# Sheet1.net
KiCad netlist of a schematic drawn in Altium Designer
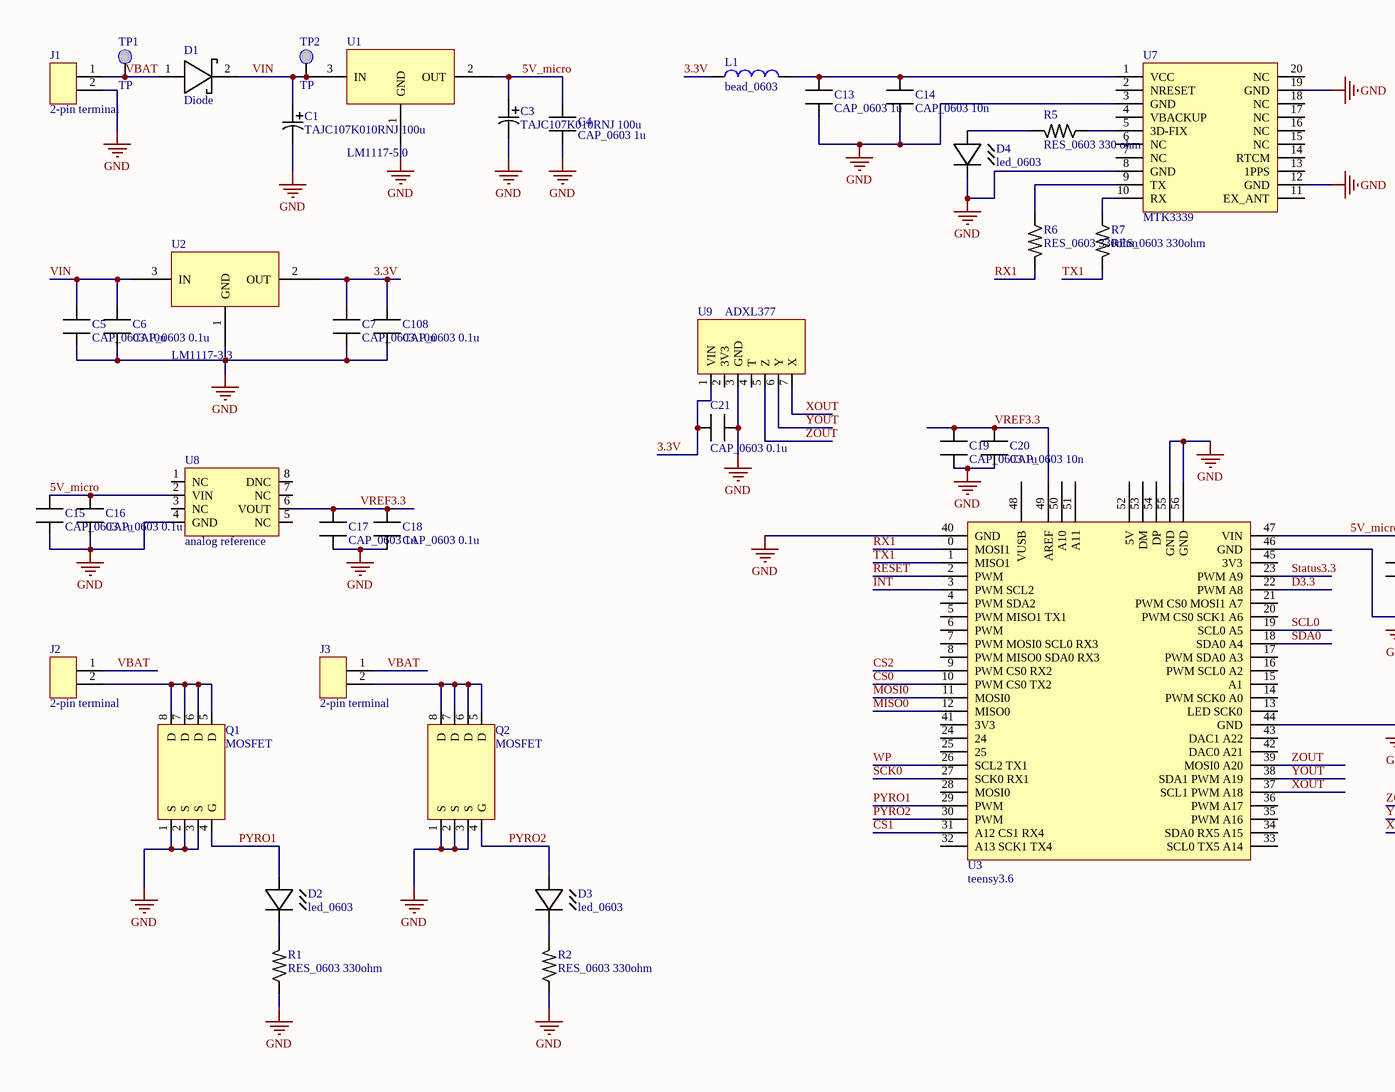
[diagram p0: Sheet1.SchDoc, left]
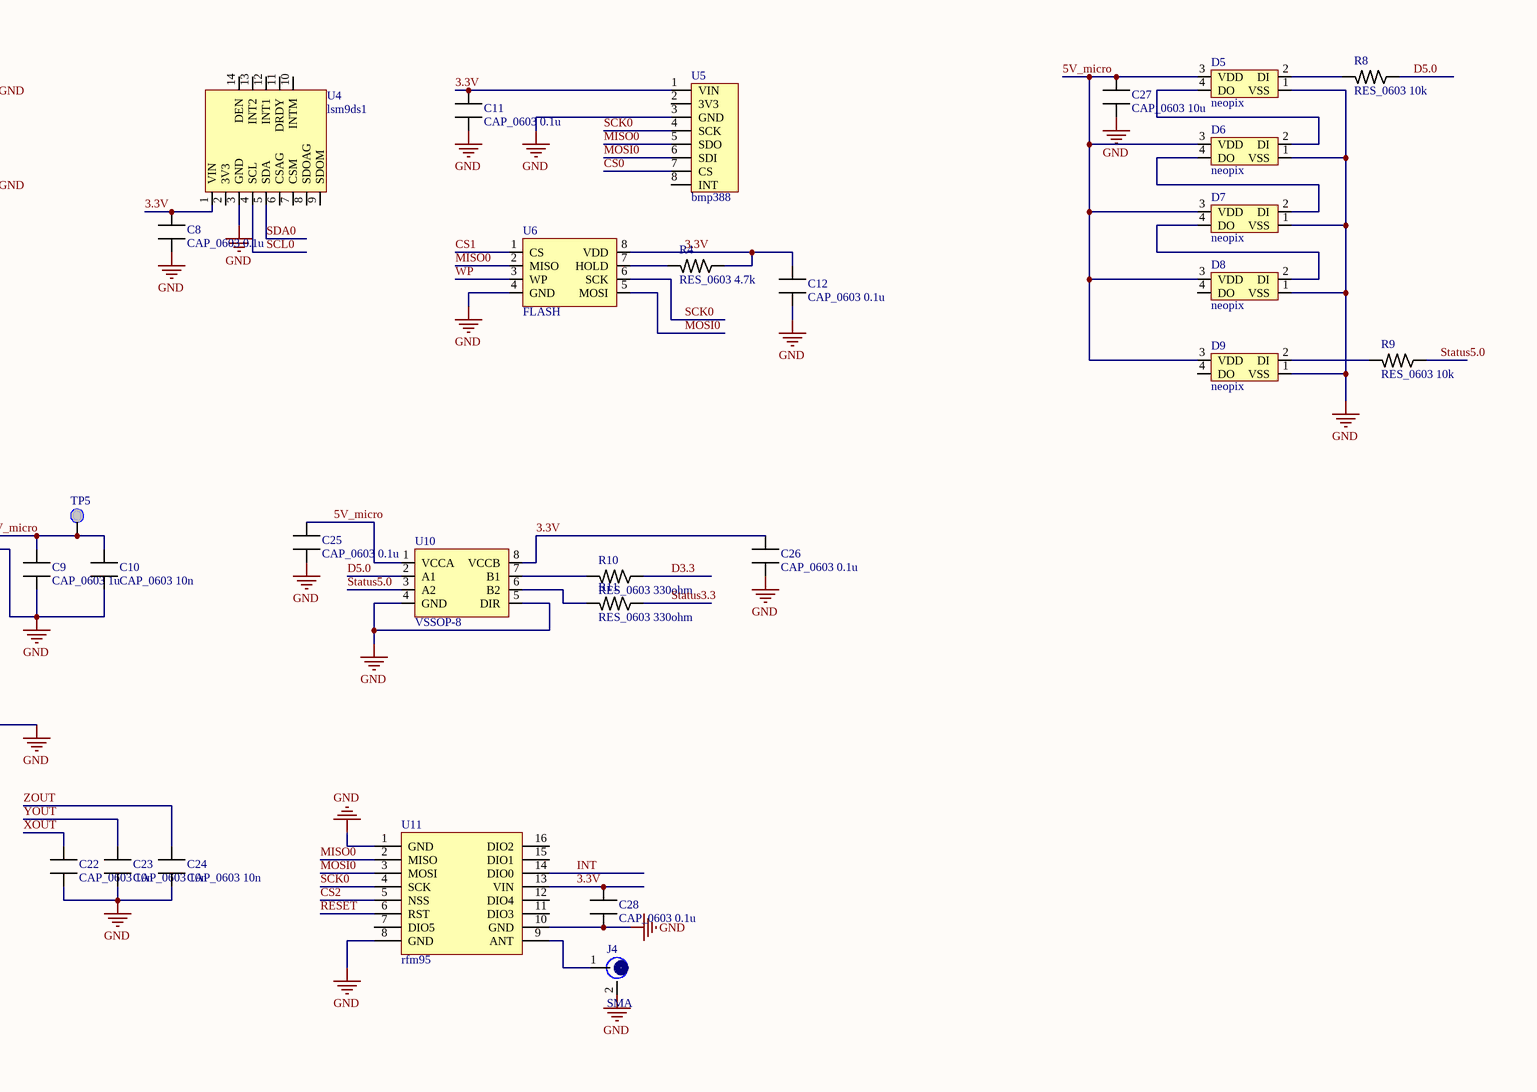
[diagram p1: Sheet1.SchDoc, right]

(export (version "E")
  (design (tool "Eeschema 10.0.6"))
  (components
    (comp (ref "C1")
      (value "TAJC107K010RNJ 100u")
      (footprint "TAJC")
      (description "100u")
      (fields
        (field (name "MANUFACTURER_PART_NUMBER") "TAJC107K010RNJ")
        (field (name "COPYRIGHT") "Copyright (C) 2018 Accelerated Designs. All rights reserved")
      )
      (libsource (lib "teensy_Integrated_Library1") (part "TAJC107K010RNJ"))
    )
    (comp (ref "C3")
      (value "TAJC107K010RNJ 100u")
      (footprint "TAJC")
      (description "No Description Available")
      (fields
        (field (name "MANUFACTURER_PART_NUMBER") "TAJC107K010RNJ")
        (field (name "COPYRIGHT") "Copyright (C) 2018 Accelerated Designs. All rights reserved")
      )
      (libsource (lib "teensy_Integrated_Library1") (part "TAJC107K010RNJ"))
    )
    (comp (ref "C4")
      (value "CAP_0603 1u")
      (footprint "CAP_0603")
      (description "CAP_0603")
      (libsource (lib "teensy_Integrated_Library1") (part "CAP_0603"))
    )
    (comp (ref "C5")
      (value "CAP_0603 10u")
      (footprint "CAP_0603")
      (description "CAP_0603")
      (libsource (lib "teensy_Integrated_Library1") (part "CAP_0603"))
    )
    (comp (ref "C6")
      (value "CAP_0603 0.1u")
      (footprint "CAP_0603")
      (description "CAP_0603")
      (libsource (lib "teensy_Integrated_Library1") (part "CAP_0603"))
    )
    (comp (ref "C7")
      (value "CAP_0603 10u")
      (footprint "CAP_0603")
      (description "CAP_0603")
      (libsource (lib "teensy_Integrated_Library1") (part "CAP_0603"))
    )
    (comp (ref "C8")
      (value "CAP_0603 0.1u")
      (footprint "CAP_0603")
      (description "CAP_0603")
      (libsource (lib "teensy_Integrated_Library1") (part "CAP_0603"))
    )
    (comp (ref "C9")
      (value "CAP_0603 1u")
      (footprint "CAP_0603")
      (description "CAP_0603")
      (libsource (lib "teensy_Integrated_Library1") (part "CAP_0603"))
    )
    (comp (ref "C10")
      (value "CAP_0603 10n")
      (footprint "CAP_0603")
      (description "CAP_0603")
      (libsource (lib "teensy_Integrated_Library1") (part "CAP_0603"))
    )
    (comp (ref "C11")
      (value "CAP_0603 0.1u")
      (footprint "CAP_0603")
      (description "CAP_0603")
      (libsource (lib "teensy_Integrated_Library1") (part "CAP_0603"))
    )
    (comp (ref "C12")
      (value "CAP_0603 0.1u")
      (footprint "CAP_0603")
      (description "CAP_0603")
      (libsource (lib "teensy_Integrated_Library1") (part "CAP_0603"))
    )
    (comp (ref "C13")
      (value "CAP_0603 1u")
      (footprint "CAP_0603")
      (description "CAP_0603")
      (libsource (lib "teensy_Integrated_Library1") (part "CAP_0603"))
    )
    (comp (ref "C14")
      (value "CAP_0603 10n")
      (footprint "CAP_0603")
      (description "CAP_0603")
      (libsource (lib "teensy_Integrated_Library1") (part "CAP_0603"))
    )
    (comp (ref "C15")
      (value "CAP_0603 1u")
      (footprint "CAP_0603")
      (description "CAP_0603")
      (libsource (lib "teensy_Integrated_Library1") (part "CAP_0603"))
    )
    (comp (ref "C16")
      (value "CAP_0603 0.1u")
      (footprint "CAP_0603")
      (description "CAP_0603")
      (libsource (lib "teensy_Integrated_Library1") (part "CAP_0603"))
    )
    (comp (ref "C17")
      (value "CAP_0603 1u")
      (footprint "CAP_0603")
      (description "CAP_0603")
      (libsource (lib "teensy_Integrated_Library1") (part "CAP_0603"))
    )
    (comp (ref "C18")
      (value "CAP_0603 0.1u")
      (footprint "CAP_0603")
      (description "CAP_0603")
      (libsource (lib "teensy_Integrated_Library1") (part "CAP_0603"))
    )
    (comp (ref "C19")
      (value "CAP_0603 1u")
      (footprint "CAP_0603")
      (description "CAP_0603")
      (libsource (lib "teensy_Integrated_Library1") (part "CAP_0603"))
    )
    (comp (ref "C20")
      (value "CAP_0603 10n")
      (footprint "CAP_0603")
      (description "CAP_0603")
      (libsource (lib "teensy_Integrated_Library1") (part "CAP_0603"))
    )
    (comp (ref "C21")
      (value "CAP_0603 0.1u")
      (footprint "CAP_0603")
      (description "CAP_0603")
      (libsource (lib "teensy_Integrated_Library1") (part "CAP_0603"))
    )
    (comp (ref "C22")
      (value "CAP_0603 10n")
      (footprint "CAP_0603")
      (description "CAP_0603")
      (libsource (lib "teensy_Integrated_Library1") (part "CAP_0603"))
    )
    (comp (ref "C23")
      (value "CAP_0603 10n")
      (footprint "CAP_0603")
      (description "CAP_0603")
      (libsource (lib "teensy_Integrated_Library1") (part "CAP_0603"))
    )
    (comp (ref "C24")
      (value "CAP_0603 10n")
      (footprint "CAP_0603")
      (description "CAP_0603")
      (libsource (lib "teensy_Integrated_Library1") (part "CAP_0603"))
    )
    (comp (ref "C25")
      (value "CAP_0603 0.1u")
      (footprint "CAP_0603")
      (description "CAP_0603")
      (libsource (lib "teensy_Integrated_Library1") (part "CAP_0603"))
    )
    (comp (ref "C26")
      (value "CAP_0603 0.1u")
      (footprint "CAP_0603")
      (description "CAP_0603")
      (libsource (lib "teensy_Integrated_Library1") (part "CAP_0603"))
    )
    (comp (ref "C27")
      (value "CAP_0603 10u")
      (footprint "CAP_0603")
      (description "CAP_0603")
      (libsource (lib "teensy_Integrated_Library1") (part "CAP_0603"))
    )
    (comp (ref "C28")
      (value "CAP_0603 0.1u")
      (footprint "CAP_0603")
      (description "CAP_0603")
      (libsource (lib "teensy_Integrated_Library1") (part "CAP_0603"))
    )
    (comp (ref "C108")
      (value "CAP_0603 0.1u")
      (footprint "CAP_0603")
      (description "CAP_0603")
      (libsource (lib "teensy_Integrated_Library1") (part "CAP_0603"))
    )
    (comp (ref "D1")
      (value "Diode")
      (footprint "RBR3LAM60BTF_diode")
      (libsource (lib "teensy_Integrated_Library1") (part "Diode"))
    )
    (comp (ref "D2")
      (value "led_0603")
      (footprint "LED_0603")
      (libsource (lib "teensy_Integrated_Library1") (part "led_0603"))
    )
    (comp (ref "D3")
      (value "led_0603")
      (footprint "LED_0603")
      (libsource (lib "teensy_Integrated_Library1") (part "led_0603"))
    )
    (comp (ref "D4")
      (value "led_0603")
      (footprint "LED_0603")
      (libsource (lib "teensy_Integrated_Library1") (part "led_0603"))
    )
    (comp (ref "D5")
      (value "neopix")
      (footprint "neopix")
      (libsource (lib "teensy_Integrated_Library1") (part "neopix"))
    )
    (comp (ref "D6")
      (value "neopix")
      (footprint "neopix")
      (libsource (lib "teensy_Integrated_Library1") (part "neopix"))
    )
    (comp (ref "D7")
      (value "neopix")
      (footprint "neopix")
      (libsource (lib "teensy_Integrated_Library1") (part "neopix"))
    )
    (comp (ref "D8")
      (value "neopix")
      (footprint "neopix")
      (libsource (lib "teensy_Integrated_Library1") (part "neopix"))
    )
    (comp (ref "D9")
      (value "neopix")
      (footprint "neopix")
      (libsource (lib "teensy_Integrated_Library1") (part "neopix"))
    )
    (comp (ref "J1")
      (value "2-pin terminal")
      (footprint "2-pin terminal")
      (libsource (lib "teensy_Integrated_Library1") (part "2-pin terminal"))
    )
    (comp (ref "J2")
      (value "2-pin terminal")
      (footprint "2-pin terminal")
      (libsource (lib "teensy_Integrated_Library1") (part "2-pin terminal"))
    )
    (comp (ref "J3")
      (value "2-pin terminal")
      (footprint "2-pin terminal")
      (libsource (lib "teensy_Integrated_Library1") (part "2-pin terminal"))
    )
    (comp (ref "J4")
      (value "SMA")
      (footprint "SMA")
      (libsource (lib "teensy_Integrated_Library1") (part "SMA"))
    )
    (comp (ref "L1")
      (value "bead_0603")
      (footprint "BEAD_0603")
      (libsource (lib "teensy_Integrated_Library1") (part "bead_0603"))
    )
    (comp (ref "Q1")
      (value "MOSFET")
      (footprint "8-SOIC")
      (libsource (lib "teensy_Integrated_Library1") (part "IRL6342TRPBFCT-ND"))
    )
    (comp (ref "Q2")
      (value "MOSFET")
      (footprint "8-SOIC")
      (libsource (lib "teensy_Integrated_Library1") (part "IRL6342TRPBFCT-ND"))
    )
    (comp (ref "R1")
      (value "RES_0603 330ohm")
      (footprint "RES_0603")
      (description "RES_0603 1/8 W")
      (libsource (lib "teensy_Integrated_Library1") (part "RES_0603"))
    )
    (comp (ref "R2")
      (value "RES_0603 330ohm")
      (footprint "RES_0603")
      (description "RES_0603 1/8 W")
      (libsource (lib "teensy_Integrated_Library1") (part "RES_0603"))
    )
    (comp (ref "R4")
      (value "RES_0603 4.7k")
      (footprint "RES_0603")
      (description "RES_0603 1/8 W")
      (libsource (lib "teensy_Integrated_Library1") (part "RES_0603"))
    )
    (comp (ref "R5")
      (value "RES_0603 330 ohm")
      (footprint "RES_0603")
      (description "RES_0603 1/8 W")
      (libsource (lib "teensy_Integrated_Library1") (part "RES_0603"))
    )
    (comp (ref "R6")
      (value "RES_0603 330ohm")
      (footprint "RES_0603")
      (description "RES_0603 1/8 W")
      (libsource (lib "teensy_Integrated_Library1") (part "RES_0603"))
    )
    (comp (ref "R7")
      (value "RES_0603 330ohm")
      (footprint "RES_0603")
      (description "RES_0603 1/8 W")
      (libsource (lib "teensy_Integrated_Library1") (part "RES_0603"))
    )
    (comp (ref "R8")
      (value "RES_0603 10k")
      (footprint "RES_0603")
      (description "RES_0603 1/8 W")
      (libsource (lib "teensy_Integrated_Library1") (part "RES_0603"))
    )
    (comp (ref "R9")
      (value "RES_0603 10k")
      (footprint "RES_0603")
      (description "RES_0603 1/8 W")
      (libsource (lib "teensy_Integrated_Library1") (part "RES_0603"))
    )
    (comp (ref "R10")
      (value "RES_0603 330ohm")
      (footprint "RES_0603")
      (description "RES_0603 1/8 W")
      (libsource (lib "teensy_Integrated_Library1") (part "RES_0603"))
    )
    (comp (ref "R11")
      (value "RES_0603 330ohm")
      (footprint "RES_0603")
      (description "RES_0603 1/8 W")
      (libsource (lib "teensy_Integrated_Library1") (part "RES_0603"))
    )
    (comp (ref "TP1")
      (value "TP")
      (footprint "TP")
      (libsource (lib "teensy_Integrated_Library1") (part "TP"))
    )
    (comp (ref "TP2")
      (value "TP")
      (footprint "TP")
      (libsource (lib "teensy_Integrated_Library1") (part "TP"))
    )
    (comp (ref "TP5")
      (value "TP")
      (footprint "TP")
      (libsource (lib "teensy_Integrated_Library1") (part "TP"))
    )
    (comp (ref "U1")
      (value "LM1117-5.0")
      (footprint "LM1117-5.0")
      (libsource (lib "teensy_Integrated_Library1") (part "LM1117-5.0"))
    )
    (comp (ref "U2")
      (value "LM1117-3.3")
      (footprint "LM1117-5.0")
      (libsource (lib "teensy_Integrated_Library1") (part "LM1117-5.0"))
    )
    (comp (ref "U3")
      (value "teensy3.6")
      (footprint "teensy3.6_1")
      (libsource (lib "teensy_Integrated_Library1") (part "teensy3.6_1"))
    )
    (comp (ref "U4")
      (value "lsm9ds1")
      (footprint "lsm9ds1")
      (libsource (lib "teensy_Integrated_Library1") (part "lsm9ds1"))
    )
    (comp (ref "U5")
      (value "bmp388")
      (footprint "bmp388")
      (libsource (lib "teensy_Integrated_Library1") (part "bmp388"))
    )
    (comp (ref "U6")
      (value "FLASH")
      (footprint "8-SOIC")
      (libsource (lib "teensy_Integrated_Library1") (part "MB85RS64V"))
    )
    (comp (ref "U7")
      (value "MTK3339")
      (footprint "MTK3339")
      (libsource (lib "teensy_Integrated_Library1") (part "MTK3339"))
    )
    (comp (ref "U8")
      (value "analog reference")
      (footprint "ADR4533")
      (libsource (lib "teensy_Integrated_Library1") (part "ADR4533"))
    )
    (comp (ref "U9")
      (value "ADXL377")
      (footprint "ADXL377")
      (libsource (lib "teensy_Integrated_Library1") (part "ADXL377"))
    )
    (comp (ref "U10")
      (value "VSSOP-8")
      (footprint "TSOP65P400X130-8M")
      (libsource (lib "teensy_Integrated_Library1") (part "SN74LVC2T45"))
    )
    (comp (ref "U11")
      (value "rfm95")
      (footprint "rfm95")
      (libsource (lib "teensy_Integrated_Library1") (part "rfm95"))
    )
  )
  (nets
    (net (code "1") (name "/3.3V") (class "Default")
      (node (ref "C108") (pin "2") (pinfunction "2_2") (pintype "passive"))
      (node (ref "C11") (pin "2") (pinfunction "2_2") (pintype "passive"))
      (node (ref "C12") (pin "2") (pinfunction "2_2") (pintype "passive"))
      (node (ref "C21") (pin "2") (pinfunction "2_2") (pintype "passive"))
      (node (ref "C26") (pin "2") (pinfunction "2_2") (pintype "passive"))
      (node (ref "C28") (pin "2") (pinfunction "2_2") (pintype "passive"))
      (node (ref "C7") (pin "2") (pinfunction "2_2") (pintype "passive"))
      (node (ref "C8") (pin "2") (pinfunction "2_2") (pintype "passive"))
      (node (ref "L1") (pin "1") (pinfunction "1_1") (pintype "passive"))
      (node (ref "R4") (pin "1") (pinfunction "1_1") (pintype "passive"))
      (node (ref "U10") (pin "8") (pinfunction "VCCB_8") (pintype "passive"))
      (node (ref "U11") (pin "13") (pinfunction "VIN_13") (pintype "passive"))
      (node (ref "U2") (pin "2") (pinfunction "OUT_2") (pintype "passive"))
      (node (ref "U4") (pin "1") (pinfunction "VIN_1") (pintype "passive"))
      (node (ref "U5") (pin "1") (pinfunction "VIN_1") (pintype "passive"))
      (node (ref "U6") (pin "8") (pinfunction "VDD_8") (pintype "passive"))
      (node (ref "U9") (pin "1") (pinfunction "VIN_1") (pintype "passive"))
    )
    (net (code "2") (name "/5V_micro") (class "Default")
      (node (ref "C10") (pin "2") (pinfunction "2_2") (pintype "passive"))
      (node (ref "C15") (pin "2") (pinfunction "2_2") (pintype "passive"))
      (node (ref "C16") (pin "2") (pinfunction "2_2") (pintype "passive"))
      (node (ref "C25") (pin "2") (pinfunction "2_2") (pintype "passive"))
      (node (ref "C27") (pin "2") (pinfunction "2_2") (pintype "passive"))
      (node (ref "C3") (pin "1") (pinfunction "1_1") (pintype "passive"))
      (node (ref "C4") (pin "2") (pinfunction "2_2") (pintype "passive"))
      (node (ref "C9") (pin "2") (pinfunction "2_2") (pintype "passive"))
      (node (ref "D5") (pin "3") (pinfunction "VDD_3") (pintype "passive"))
      (node (ref "D6") (pin "3") (pinfunction "VDD_3") (pintype "passive"))
      (node (ref "D7") (pin "3") (pinfunction "VDD_3") (pintype "passive"))
      (node (ref "D8") (pin "3") (pinfunction "VDD_3") (pintype "passive"))
      (node (ref "D9") (pin "3") (pinfunction "VDD_3") (pintype "passive"))
      (node (ref "TP5") (pin "1") (pinfunction "1_1") (pintype "passive"))
      (node (ref "U1") (pin "2") (pinfunction "OUT_2") (pintype "passive"))
      (node (ref "U10") (pin "1") (pinfunction "VCCA_1") (pintype "passive"))
      (node (ref "U3") (pin "47") (pinfunction "VIN_47") (pintype "passive"))
      (node (ref "U8") (pin "2") (pinfunction "VIN_2") (pintype "passive"))
    )
    (net (code "3") (name "/CS0") (class "Default")
      (node (ref "U3") (pin "10") (pinfunction "PWM_CS0_TX2_10") (pintype "passive"))
      (node (ref "U5") (pin "7") (pinfunction "CS_7") (pintype "passive"))
    )
    (net (code "4") (name "/CS1") (class "Default")
      (node (ref "U3") (pin "31") (pinfunction "A12_CS1_RX4_31") (pintype "passive"))
      (node (ref "U6") (pin "1") (pinfunction "CS_1") (pintype "passive"))
    )
    (net (code "5") (name "/CS2") (class "Default")
      (node (ref "U11") (pin "5") (pinfunction "NSS_5") (pintype "passive"))
      (node (ref "U3") (pin "9") (pinfunction "PWM_CS0_RX2_9") (pintype "passive"))
    )
    (net (code "6") (name "/D3.3") (class "Default")
      (node (ref "R10") (pin "1") (pinfunction "1_1") (pintype "passive"))
      (node (ref "U3") (pin "22") (pinfunction "PWM_A8_22") (pintype "passive"))
    )
    (net (code "7") (name "/D5.0") (class "Default")
      (node (ref "R8") (pin "1") (pinfunction "1_1") (pintype "passive"))
      (node (ref "U10") (pin "2") (pinfunction "A1_2") (pintype "passive"))
    )
    (net (code "8") (name "/INT") (class "Default")
      (node (ref "U11") (pin "14") (pinfunction "DIO0_14") (pintype "passive"))
      (node (ref "U3") (pin "3") (pinfunction "PWM_SCL2_3") (pintype "passive"))
    )
    (net (code "9") (name "/MISO0") (class "Default")
      (node (ref "U11") (pin "2") (pinfunction "MISO_2") (pintype "passive"))
      (node (ref "U3") (pin "12") (pinfunction "MISO0_12") (pintype "passive"))
      (node (ref "U5") (pin "5") (pinfunction "SDO_5") (pintype "passive"))
      (node (ref "U6") (pin "2") (pinfunction "MISO_2") (pintype "passive"))
    )
    (net (code "10") (name "/MOSI0") (class "Default")
      (node (ref "U11") (pin "3") (pinfunction "MOSI_3") (pintype "passive"))
      (node (ref "U3") (pin "11") (pinfunction "MOSI0_11") (pintype "passive"))
      (node (ref "U5") (pin "6") (pinfunction "SDI_6") (pintype "passive"))
      (node (ref "U6") (pin "5") (pinfunction "MOSI_5") (pintype "passive"))
    )
    (net (code "11") (name "/PYRO1") (class "Default")
      (node (ref "D2") (pin "1") (pinfunction "1_1") (pintype "passive"))
      (node (ref "Q1") (pin "4") (pinfunction "G_4") (pintype "passive"))
      (node (ref "U3") (pin "29") (pinfunction "PWM_29") (pintype "passive"))
    )
    (net (code "12") (name "/PYRO2") (class "Default")
      (node (ref "D3") (pin "1") (pinfunction "1_1") (pintype "passive"))
      (node (ref "Q2") (pin "4") (pinfunction "G_4") (pintype "passive"))
      (node (ref "U3") (pin "30") (pinfunction "PWM_30") (pintype "passive"))
    )
    (net (code "13") (name "/RESET") (class "Default")
      (node (ref "U11") (pin "6") (pinfunction "RST_6") (pintype "passive"))
      (node (ref "U3") (pin "2") (pinfunction "PWM_2") (pintype "passive"))
    )
    (net (code "14") (name "/RX1") (class "Default")
      (node (ref "R6") (pin "2") (pinfunction "2_2") (pintype "passive"))
      (node (ref "U3") (pin "0") (pinfunction "MOSI1_0") (pintype "passive"))
    )
    (net (code "15") (name "/SCK0") (class "Default")
      (node (ref "U11") (pin "4") (pinfunction "SCK_4") (pintype "passive"))
      (node (ref "U3") (pin "27") (pinfunction "SCK0_RX1_27") (pintype "passive"))
      (node (ref "U5") (pin "4") (pinfunction "SCK_4") (pintype "passive"))
      (node (ref "U6") (pin "6") (pinfunction "SCK_6") (pintype "passive"))
    )
    (net (code "16") (name "/SCL0") (class "Default")
      (node (ref "U3") (pin "19") (pinfunction "SCL0_A5_19") (pintype "passive"))
      (node (ref "U4") (pin "4") (pinfunction "SCL_4") (pintype "passive"))
    )
    (net (code "17") (name "/SDA0") (class "Default")
      (node (ref "U3") (pin "18") (pinfunction "SDA0_A4_18") (pintype "passive"))
      (node (ref "U4") (pin "5") (pinfunction "SDA_5") (pintype "passive"))
    )
    (net (code "18") (name "/Status3.3") (class "Default")
      (node (ref "R11") (pin "1") (pinfunction "1_1") (pintype "passive"))
      (node (ref "U3") (pin "23") (pinfunction "PWM_A9_23") (pintype "passive"))
    )
    (net (code "19") (name "/Status5.0") (class "Default")
      (node (ref "R9") (pin "1") (pinfunction "1_1") (pintype "passive"))
      (node (ref "U10") (pin "3") (pinfunction "A2_3") (pintype "passive"))
    )
    (net (code "20") (name "/TX1") (class "Default")
      (node (ref "R7") (pin "2") (pinfunction "2_2") (pintype "passive"))
      (node (ref "U3") (pin "1") (pinfunction "MISO1_1") (pintype "passive"))
    )
    (net (code "21") (name "/VBAT") (class "Default")
      (node (ref "D1") (pin "1") (pinfunction "1_1") (pintype "passive"))
      (node (ref "J1") (pin "1") (pinfunction "1_1") (pintype "passive"))
      (node (ref "J2") (pin "1") (pinfunction "1_1") (pintype "passive"))
      (node (ref "J3") (pin "1") (pinfunction "1_1") (pintype "passive"))
      (node (ref "TP1") (pin "1") (pinfunction "1_1") (pintype "passive"))
    )
    (net (code "22") (name "/VIN") (class "Default")
      (node (ref "C1") (pin "1") (pinfunction "1_1") (pintype "passive"))
      (node (ref "C5") (pin "2") (pinfunction "2_2") (pintype "passive"))
      (node (ref "C6") (pin "2") (pinfunction "2_2") (pintype "passive"))
      (node (ref "D1") (pin "2") (pinfunction "2_2") (pintype "passive"))
      (node (ref "TP2") (pin "1") (pinfunction "1_1") (pintype "passive"))
      (node (ref "U1") (pin "3") (pinfunction "IN_3") (pintype "passive"))
      (node (ref "U2") (pin "3") (pinfunction "IN_3") (pintype "passive"))
    )
    (net (code "23") (name "/VREF3.3") (class "Default")
      (node (ref "C17") (pin "2") (pinfunction "2_2") (pintype "passive"))
      (node (ref "C18") (pin "2") (pinfunction "2_2") (pintype "passive"))
      (node (ref "C19") (pin "2") (pinfunction "2_2") (pintype "passive"))
      (node (ref "C20") (pin "2") (pinfunction "2_2") (pintype "passive"))
      (node (ref "U3") (pin "49") (pinfunction "AREF_49") (pintype "passive"))
      (node (ref "U8") (pin "6") (pinfunction "VOUT_6") (pintype "passive"))
    )
    (net (code "24") (name "/WP") (class "Default")
      (node (ref "U3") (pin "26") (pinfunction "SCL2_TX1_26") (pintype "passive"))
      (node (ref "U6") (pin "3") (pinfunction "WP_3") (pintype "passive"))
    )
    (net (code "25") (name "/XOUT") (class "Default")
      (node (ref "C22") (pin "2") (pinfunction "2_2") (pintype "passive"))
      (node (ref "U3") (pin "37") (pinfunction "SCL1_PWM_A18_37") (pintype "passive"))
      (node (ref "U9") (pin "7") (pinfunction "X_7") (pintype "passive"))
    )
    (net (code "26") (name "/YOUT") (class "Default")
      (node (ref "C23") (pin "2") (pinfunction "2_2") (pintype "passive"))
      (node (ref "U3") (pin "38") (pinfunction "SDA1_PWM_A19_38") (pintype "passive"))
      (node (ref "U9") (pin "6") (pinfunction "Y_6") (pintype "passive"))
    )
    (net (code "27") (name "/ZOUT") (class "Default")
      (node (ref "C24") (pin "2") (pinfunction "2_2") (pintype "passive"))
      (node (ref "U3") (pin "39") (pinfunction "MOSI0_A20_39") (pintype "passive"))
      (node (ref "U9") (pin "5") (pinfunction "Z_5") (pintype "passive"))
    )
    (net (code "28") (name "GND") (class "Default")
      (node (ref "C1") (pin "2") (pinfunction "2_2") (pintype "passive"))
      (node (ref "C10") (pin "1") (pinfunction "1_1") (pintype "passive"))
      (node (ref "C108") (pin "1") (pinfunction "1_1") (pintype "passive"))
      (node (ref "C11") (pin "1") (pinfunction "1_1") (pintype "passive"))
      (node (ref "C12") (pin "1") (pinfunction "1_1") (pintype "passive"))
      (node (ref "C13") (pin "1") (pinfunction "1_1") (pintype "passive"))
      (node (ref "C14") (pin "1") (pinfunction "1_1") (pintype "passive"))
      (node (ref "C15") (pin "1") (pinfunction "1_1") (pintype "passive"))
      (node (ref "C16") (pin "1") (pinfunction "1_1") (pintype "passive"))
      (node (ref "C17") (pin "1") (pinfunction "1_1") (pintype "passive"))
      (node (ref "C18") (pin "1") (pinfunction "1_1") (pintype "passive"))
      (node (ref "C19") (pin "1") (pinfunction "1_1") (pintype "passive"))
      (node (ref "C20") (pin "1") (pinfunction "1_1") (pintype "passive"))
      (node (ref "C21") (pin "1") (pinfunction "1_1") (pintype "passive"))
      (node (ref "C22") (pin "1") (pinfunction "1_1") (pintype "passive"))
      (node (ref "C23") (pin "1") (pinfunction "1_1") (pintype "passive"))
      (node (ref "C24") (pin "1") (pinfunction "1_1") (pintype "passive"))
      (node (ref "C25") (pin "1") (pinfunction "1_1") (pintype "passive"))
      (node (ref "C26") (pin "1") (pinfunction "1_1") (pintype "passive"))
      (node (ref "C27") (pin "1") (pinfunction "1_1") (pintype "passive"))
      (node (ref "C28") (pin "1") (pinfunction "1_1") (pintype "passive"))
      (node (ref "C3") (pin "2") (pinfunction "2_2") (pintype "passive"))
      (node (ref "C4") (pin "1") (pinfunction "1_1") (pintype "passive"))
      (node (ref "C5") (pin "1") (pinfunction "1_1") (pintype "passive"))
      (node (ref "C6") (pin "1") (pinfunction "1_1") (pintype "passive"))
      (node (ref "C7") (pin "1") (pinfunction "1_1") (pintype "passive"))
      (node (ref "C8") (pin "1") (pinfunction "1_1") (pintype "passive"))
      (node (ref "C9") (pin "1") (pinfunction "1_1") (pintype "passive"))
      (node (ref "D4") (pin "2") (pinfunction "2_2") (pintype "passive"))
      (node (ref "D5") (pin "1") (pinfunction "VSS_1") (pintype "passive"))
      (node (ref "D6") (pin "1") (pinfunction "VSS_1") (pintype "passive"))
      (node (ref "D7") (pin "1") (pinfunction "VSS_1") (pintype "passive"))
      (node (ref "D8") (pin "1") (pinfunction "VSS_1") (pintype "passive"))
      (node (ref "D9") (pin "1") (pinfunction "VSS_1") (pintype "passive"))
      (node (ref "J1") (pin "2") (pinfunction "2_2") (pintype "passive"))
      (node (ref "J4") (pin "2") (pinfunction "正弦波失真度调整_2") (pintype "passive"))
      (node (ref "Q1") (pin "1") (pinfunction "S_1") (pintype "passive"))
      (node (ref "Q1") (pin "2") (pinfunction "S_2") (pintype "passive"))
      (node (ref "Q1") (pin "3") (pinfunction "S_3") (pintype "passive"))
      (node (ref "Q2") (pin "1") (pinfunction "S_1") (pintype "passive"))
      (node (ref "Q2") (pin "2") (pinfunction "S_2") (pintype "passive"))
      (node (ref "Q2") (pin "3") (pinfunction "S_3") (pintype "passive"))
      (node (ref "R1") (pin "1") (pinfunction "1_1") (pintype "passive"))
      (node (ref "R2") (pin "1") (pinfunction "1_1") (pintype "passive"))
      (node (ref "U1") (pin "1") (pinfunction "GND_1") (pintype "passive"))
      (node (ref "U10") (pin "4") (pinfunction "GND_4") (pintype "passive"))
      (node (ref "U10") (pin "5") (pinfunction "DIR_5") (pintype "passive"))
      (node (ref "U11") (pin "1") (pinfunction "GND_1") (pintype "passive"))
      (node (ref "U11") (pin "10") (pinfunction "GND_10") (pintype "passive"))
      (node (ref "U11") (pin "8") (pinfunction "GND_8") (pintype "passive"))
      (node (ref "U2") (pin "1") (pinfunction "GND_1") (pintype "passive"))
      (node (ref "U3") (pin "40") (pinfunction "GND_40") (pintype "passive"))
      (node (ref "U3") (pin "44") (pinfunction "GND_44") (pintype "passive"))
      (node (ref "U3") (pin "46") (pinfunction "GND_46") (pintype "passive"))
      (node (ref "U3") (pin "55") (pinfunction "GND_55") (pintype "passive"))
      (node (ref "U3") (pin "56") (pinfunction "GND_56") (pintype "passive"))
      (node (ref "U4") (pin "3") (pinfunction "GND_3") (pintype "passive"))
      (node (ref "U5") (pin "3") (pinfunction "GND_3") (pintype "passive"))
      (node (ref "U6") (pin "4") (pinfunction "GND_4") (pintype "passive"))
      (node (ref "U7") (pin "12") (pinfunction "GND_12") (pintype "passive"))
      (node (ref "U7") (pin "19") (pinfunction "GND_19") (pintype "passive"))
      (node (ref "U7") (pin "3") (pinfunction "GND_3") (pintype "passive"))
      (node (ref "U7") (pin "8") (pinfunction "GND_8") (pintype "passive"))
      (node (ref "U8") (pin "4") (pinfunction "GND_4") (pintype "passive"))
      (node (ref "U9") (pin "3") (pinfunction "GND_3") (pintype "passive"))
    )
    (net (code "29") (name "Net-(D2-Pad2)") (class "Default")
      (node (ref "D2") (pin "2") (pinfunction "2_2") (pintype "passive"))
      (node (ref "R1") (pin "2") (pinfunction "2_2") (pintype "passive"))
    )
    (net (code "30") (name "Net-(D3-Pad2)") (class "Default")
      (node (ref "D3") (pin "2") (pinfunction "2_2") (pintype "passive"))
      (node (ref "R2") (pin "2") (pinfunction "2_2") (pintype "passive"))
    )
    (net (code "31") (name "Net-(D4-Pad1)") (class "Default")
      (node (ref "D4") (pin "1") (pinfunction "1_1") (pintype "passive"))
      (node (ref "R5") (pin "2") (pinfunction "2_2") (pintype "passive"))
    )
    (net (code "32") (name "Net-(D5-DI)") (class "Default")
      (node (ref "D5") (pin "2") (pinfunction "DI_2") (pintype "passive"))
      (node (ref "R8") (pin "2") (pinfunction "2_2") (pintype "passive"))
    )
    (net (code "33") (name "Net-(D5-DO)") (class "Default")
      (node (ref "D5") (pin "4") (pinfunction "DO_4") (pintype "passive"))
      (node (ref "D6") (pin "2") (pinfunction "DI_2") (pintype "passive"))
    )
    (net (code "34") (name "Net-(D6-DO)") (class "Default")
      (node (ref "D6") (pin "4") (pinfunction "DO_4") (pintype "passive"))
      (node (ref "D7") (pin "2") (pinfunction "DI_2") (pintype "passive"))
    )
    (net (code "35") (name "Net-(D7-DO)") (class "Default")
      (node (ref "D7") (pin "4") (pinfunction "DO_4") (pintype "passive"))
      (node (ref "D8") (pin "2") (pinfunction "DI_2") (pintype "passive"))
    )
    (net (code "36") (name "Net-(D9-DI)") (class "Default")
      (node (ref "D9") (pin "2") (pinfunction "DI_2") (pintype "passive"))
      (node (ref "R9") (pin "2") (pinfunction "2_2") (pintype "passive"))
    )
    (net (code "37") (name "Net-(J2-Pad2)") (class "Default")
      (node (ref "J2") (pin "2") (pinfunction "2_2") (pintype "passive"))
      (node (ref "Q1") (pin "5") (pinfunction "D_5") (pintype "passive"))
      (node (ref "Q1") (pin "6") (pinfunction "D_6") (pintype "passive"))
      (node (ref "Q1") (pin "7") (pinfunction "D_7") (pintype "passive"))
      (node (ref "Q1") (pin "8") (pinfunction "D_8") (pintype "passive"))
    )
    (net (code "38") (name "Net-(J3-Pad2)") (class "Default")
      (node (ref "J3") (pin "2") (pinfunction "2_2") (pintype "passive"))
      (node (ref "Q2") (pin "5") (pinfunction "D_5") (pintype "passive"))
      (node (ref "Q2") (pin "6") (pinfunction "D_6") (pintype "passive"))
      (node (ref "Q2") (pin "7") (pinfunction "D_7") (pintype "passive"))
      (node (ref "Q2") (pin "8") (pinfunction "D_8") (pintype "passive"))
    )
    (net (code "39") (name "Net-(U6-HOLD)") (class "Default")
      (node (ref "R4") (pin "2") (pinfunction "2_2") (pintype "passive"))
      (node (ref "U6") (pin "7") (pinfunction "HOLD_7") (pintype "passive"))
    )
    (net (code "40") (name "Net-(U7-3D-FIX)") (class "Default")
      (node (ref "R5") (pin "1") (pinfunction "1_1") (pintype "passive"))
      (node (ref "U7") (pin "5") (pinfunction "3D-FIX_5") (pintype "passive"))
    )
    (net (code "41") (name "Net-(U7-RX)") (class "Default")
      (node (ref "R7") (pin "1") (pinfunction "1_1") (pintype "passive"))
      (node (ref "U7") (pin "10") (pinfunction "RX_10") (pintype "passive"))
    )
    (net (code "42") (name "Net-(U7-TX)") (class "Default")
      (node (ref "R6") (pin "1") (pinfunction "1_1") (pintype "passive"))
      (node (ref "U7") (pin "9") (pinfunction "TX_9") (pintype "passive"))
    )
    (net (code "43") (name "Net-(U7-VCC)") (class "Default")
      (node (ref "C13") (pin "2") (pinfunction "2_2") (pintype "passive"))
      (node (ref "C14") (pin "2") (pinfunction "2_2") (pintype "passive"))
      (node (ref "L1") (pin "2") (pinfunction "2_2") (pintype "passive"))
      (node (ref "U7") (pin "1") (pinfunction "VCC_1") (pintype "passive"))
    )
    (net (code "44") (name "Net-(U10-B1)") (class "Default")
      (node (ref "R10") (pin "2") (pinfunction "2_2") (pintype "passive"))
      (node (ref "U10") (pin "7") (pinfunction "B1_7") (pintype "passive"))
    )
    (net (code "45") (name "Net-(U10-B2)") (class "Default")
      (node (ref "R11") (pin "2") (pinfunction "2_2") (pintype "passive"))
      (node (ref "U10") (pin "6") (pinfunction "B2_6") (pintype "passive"))
    )
    (net (code "46") (name "Net-(U11-ANT)") (class "Default")
      (node (ref "J4") (pin "1") (pinfunction "正弦波失真度调整_1") (pintype "passive"))
      (node (ref "U11") (pin "9") (pinfunction "ANT_9") (pintype "passive"))
    )
    (net (code "47") (name "unconnected-(D8-DO-Pad4)") (class "Default")
      (node (ref "D8") (pin "4") (pinfunction "DO_4") (pintype "passive"))
    )
    (net (code "48") (name "unconnected-(D9-DO-Pad4)") (class "Default")
      (node (ref "D9") (pin "4") (pinfunction "DO_4") (pintype "passive"))
    )
    (net (code "49") (name "unconnected-(U3-3V3-Pad41)") (class "Default")
      (node (ref "U3") (pin "41") (pinfunction "3V3_41") (pintype "passive"))
    )
    (net (code "50") (name "unconnected-(U3-3V3-Pad45)") (class "Default")
      (node (ref "U3") (pin "45") (pinfunction "3V3_45") (pintype "passive"))
    )
    (net (code "51") (name "unconnected-(U3-5V-Pad52)") (class "Default")
      (node (ref "U3") (pin "52") (pinfunction "5V_52") (pintype "passive"))
    )
    (net (code "52") (name "unconnected-(U3-A1-Pad15)") (class "Default")
      (node (ref "U3") (pin "15") (pinfunction "A1_15") (pintype "passive"))
    )
    (net (code "53") (name "unconnected-(U3-A10-Pad50)") (class "Default")
      (node (ref "U3") (pin "50") (pinfunction "A10_50") (pintype "passive"))
    )
    (net (code "54") (name "unconnected-(U3-A11-Pad51)") (class "Default")
      (node (ref "U3") (pin "51") (pinfunction "A11_51") (pintype "passive"))
    )
    (net (code "55") (name "unconnected-(U3-A13_SCK1_TX4-Pad32)") (class "Default")
      (node (ref "U3") (pin "32") (pinfunction "A13_SCK1_TX4_32") (pintype "passive"))
    )
    (net (code "56") (name "unconnected-(U3-DAC0_A21-Pad42)") (class "Default")
      (node (ref "U3") (pin "42") (pinfunction "DAC0_A21_42") (pintype "passive"))
    )
    (net (code "57") (name "unconnected-(U3-DAC1_A22-Pad43)") (class "Default")
      (node (ref "U3") (pin "43") (pinfunction "DAC1_A22_43") (pintype "passive"))
    )
    (net (code "58") (name "unconnected-(U3-DM-Pad53)") (class "Default")
      (node (ref "U3") (pin "53") (pinfunction "DM_53") (pintype "passive"))
    )
    (net (code "59") (name "unconnected-(U3-DP-Pad54)") (class "Default")
      (node (ref "U3") (pin "54") (pinfunction "DP_54") (pintype "passive"))
    )
    (net (code "60") (name "unconnected-(U3-LED_SCK0-Pad13)") (class "Default")
      (node (ref "U3") (pin "13") (pinfunction "LED_SCK0_13") (pintype "passive"))
    )
    (net (code "61") (name "unconnected-(U3-MOSI0-Pad28)") (class "Default")
      (node (ref "U3") (pin "28") (pinfunction "MOSI0_28") (pintype "passive"))
    )
    (net (code "62") (name "unconnected-(U3-PWM-Pad6)") (class "Default")
      (node (ref "U3") (pin "6") (pinfunction "PWM_6") (pintype "passive"))
    )
    (net (code "63") (name "unconnected-(U3-PWM_A16-Pad35)") (class "Default")
      (node (ref "U3") (pin "35") (pinfunction "PWM_A16_35") (pintype "passive"))
    )
    (net (code "64") (name "unconnected-(U3-PWM_A17-Pad36)") (class "Default")
      (node (ref "U3") (pin "36") (pinfunction "PWM_A17_36") (pintype "passive"))
    )
    (net (code "65") (name "unconnected-(U3-PWM_CS0_MOSI1_A7-Pad21)") (class "Default")
      (node (ref "U3") (pin "21") (pinfunction "PWM_CS0_MOSI1_A7_21") (pintype "passive"))
    )
    (net (code "66") (name "unconnected-(U3-PWM_CS0_SCK1_A6-Pad20)") (class "Default")
      (node (ref "U3") (pin "20") (pinfunction "PWM_CS0_SCK1_A6_20") (pintype "passive"))
    )
    (net (code "67") (name "unconnected-(U3-PWM_MISO0_SDA0_RX3-Pad8)") (class "Default")
      (node (ref "U3") (pin "8") (pinfunction "PWM_MISO0_SDA0_RX3_8") (pintype "passive"))
    )
    (net (code "68") (name "unconnected-(U3-PWM_MISO1_TX1-Pad5)") (class "Default")
      (node (ref "U3") (pin "5") (pinfunction "PWM_MISO1_TX1_5") (pintype "passive"))
    )
    (net (code "69") (name "unconnected-(U3-PWM_MOSI0_SCL0_RX3-Pad7)") (class "Default")
      (node (ref "U3") (pin "7") (pinfunction "PWM_MOSI0_SCL0_RX3_7") (pintype "passive"))
    )
    (net (code "70") (name "unconnected-(U3-PWM_SCK0_A0-Pad14)") (class "Default")
      (node (ref "U3") (pin "14") (pinfunction "PWM_SCK0_A0_14") (pintype "passive"))
    )
    (net (code "71") (name "unconnected-(U3-PWM_SCL0_A2-Pad16)") (class "Default")
      (node (ref "U3") (pin "16") (pinfunction "PWM_SCL0_A2_16") (pintype "passive"))
    )
    (net (code "72") (name "unconnected-(U3-PWM_SDA0_A3-Pad17)") (class "Default")
      (node (ref "U3") (pin "17") (pinfunction "PWM_SDA0_A3_17") (pintype "passive"))
    )
    (net (code "73") (name "unconnected-(U3-PWM_SDA2-Pad4)") (class "Default")
      (node (ref "U3") (pin "4") (pinfunction "PWM_SDA2_4") (pintype "passive"))
    )
    (net (code "74") (name "unconnected-(U3-Pad24)") (class "Default")
      (node (ref "U3") (pin "24") (pinfunction "24_24") (pintype "passive"))
    )
    (net (code "75") (name "unconnected-(U3-Pad25)") (class "Default")
      (node (ref "U3") (pin "25") (pinfunction "25_25") (pintype "passive"))
    )
    (net (code "76") (name "unconnected-(U3-SCL0_TX5_A14-Pad33)") (class "Default")
      (node (ref "U3") (pin "33") (pinfunction "SCL0_TX5_A14_33") (pintype "passive"))
    )
    (net (code "77") (name "unconnected-(U3-SDA0_RX5_A15-Pad34)") (class "Default")
      (node (ref "U3") (pin "34") (pinfunction "SDA0_RX5_A15_34") (pintype "passive"))
    )
    (net (code "78") (name "unconnected-(U3-VUSB-Pad48)") (class "Default")
      (node (ref "U3") (pin "48") (pinfunction "VUSB_48") (pintype "passive"))
    )
    (net (code "79") (name "unconnected-(U4-3V3-Pad2)") (class "Default")
      (node (ref "U4") (pin "2") (pinfunction "3V3_2") (pintype "passive"))
    )
    (net (code "80") (name "unconnected-(U4-CSAG-Pad6)") (class "Default")
      (node (ref "U4") (pin "6") (pinfunction "CSAG_6") (pintype "passive"))
    )
    (net (code "81") (name "unconnected-(U4-CSM-Pad7)") (class "Default")
      (node (ref "U4") (pin "7") (pinfunction "CSM_7") (pintype "passive"))
    )
    (net (code "82") (name "unconnected-(U4-DEN-Pad14)") (class "Default")
      (node (ref "U4") (pin "14") (pinfunction "DEN_14") (pintype "passive"))
    )
    (net (code "83") (name "unconnected-(U4-DRDY-Pad11)") (class "Default")
      (node (ref "U4") (pin "11") (pinfunction "DRDY_11") (pintype "passive"))
    )
    (net (code "84") (name "unconnected-(U4-INT1-Pad12)") (class "Default")
      (node (ref "U4") (pin "12") (pinfunction "INT1_12") (pintype "passive"))
    )
    (net (code "85") (name "unconnected-(U4-INT2-Pad13)") (class "Default")
      (node (ref "U4") (pin "13") (pinfunction "INT2_13") (pintype "passive"))
    )
    (net (code "86") (name "unconnected-(U4-INTM-Pad10)") (class "Default")
      (node (ref "U4") (pin "10") (pinfunction "INTM_10") (pintype "passive"))
    )
    (net (code "87") (name "unconnected-(U4-SDOAG-Pad8)") (class "Default")
      (node (ref "U4") (pin "8") (pinfunction "SDOAG_8") (pintype "passive"))
    )
    (net (code "88") (name "unconnected-(U4-SDOM-Pad9)") (class "Default")
      (node (ref "U4") (pin "9") (pinfunction "SDOM_9") (pintype "passive"))
    )
    (net (code "89") (name "unconnected-(U5-3V3-Pad2)") (class "Default")
      (node (ref "U5") (pin "2") (pinfunction "3V3_2") (pintype "passive"))
    )
    (net (code "90") (name "unconnected-(U5-INT-Pad8)") (class "Default")
      (node (ref "U5") (pin "8") (pinfunction "INT_8") (pintype "passive"))
    )
    (net (code "91") (name "unconnected-(U7-1PPS-Pad13)") (class "Default")
      (node (ref "U7") (pin "13") (pinfunction "1PPS_13") (pintype "passive"))
    )
    (net (code "92") (name "unconnected-(U7-EX_ANT-Pad11)") (class "Default")
      (node (ref "U7") (pin "11") (pinfunction "EX_ANT_11") (pintype "passive"))
    )
    (net (code "93") (name "unconnected-(U7-NC-Pad6)") (class "Default")
      (node (ref "U7") (pin "6") (pinfunction "NC_6") (pintype "passive"))
    )
    (net (code "94") (name "unconnected-(U7-NC-Pad7)") (class "Default")
      (node (ref "U7") (pin "7") (pinfunction "NC_7") (pintype "passive"))
    )
    (net (code "95") (name "unconnected-(U7-NC-Pad15)") (class "Default")
      (node (ref "U7") (pin "15") (pinfunction "NC_15") (pintype "passive"))
    )
    (net (code "96") (name "unconnected-(U7-NC-Pad16)") (class "Default")
      (node (ref "U7") (pin "16") (pinfunction "NC_16") (pintype "passive"))
    )
    (net (code "97") (name "unconnected-(U7-NC-Pad17)") (class "Default")
      (node (ref "U7") (pin "17") (pinfunction "NC_17") (pintype "passive"))
    )
    (net (code "98") (name "unconnected-(U7-NC-Pad18)") (class "Default")
      (node (ref "U7") (pin "18") (pinfunction "NC_18") (pintype "passive"))
    )
    (net (code "99") (name "unconnected-(U7-NC-Pad20)") (class "Default")
      (node (ref "U7") (pin "20") (pinfunction "NC_20") (pintype "passive"))
    )
    (net (code "100") (name "unconnected-(U7-NRESET-Pad2)") (class "Default")
      (node (ref "U7") (pin "2") (pinfunction "NRESET_2") (pintype "passive"))
    )
    (net (code "101") (name "unconnected-(U7-RTCM-Pad14)") (class "Default")
      (node (ref "U7") (pin "14") (pinfunction "RTCM_14") (pintype "passive"))
    )
    (net (code "102") (name "unconnected-(U7-VBACKUP-Pad4)") (class "Default")
      (node (ref "U7") (pin "4") (pinfunction "VBACKUP_4") (pintype "passive"))
    )
    (net (code "103") (name "unconnected-(U8-DNC-Pad8)") (class "Default")
      (node (ref "U8") (pin "8") (pinfunction "DNC_8") (pintype "passive"))
    )
    (net (code "104") (name "unconnected-(U8-NC-Pad1)") (class "Default")
      (node (ref "U8") (pin "1") (pinfunction "NC_1") (pintype "passive"))
    )
    (net (code "105") (name "unconnected-(U8-NC-Pad3)") (class "Default")
      (node (ref "U8") (pin "3") (pinfunction "NC_3") (pintype "passive"))
    )
    (net (code "106") (name "unconnected-(U8-NC-Pad5)") (class "Default")
      (node (ref "U8") (pin "5") (pinfunction "NC_5") (pintype "passive"))
    )
    (net (code "107") (name "unconnected-(U8-NC-Pad7)") (class "Default")
      (node (ref "U8") (pin "7") (pinfunction "NC_7") (pintype "passive"))
    )
    (net (code "108") (name "unconnected-(U9-3V3-Pad2)") (class "Default")
      (node (ref "U9") (pin "2") (pinfunction "3V3_2") (pintype "passive"))
    )
    (net (code "109") (name "unconnected-(U9-T-Pad4)") (class "Default")
      (node (ref "U9") (pin "4") (pinfunction "T_4") (pintype "passive"))
    )
    (net (code "110") (name "unconnected-(U11-DIO1-Pad15)") (class "Default")
      (node (ref "U11") (pin "15") (pinfunction "DIO1_15") (pintype "passive"))
    )
    (net (code "111") (name "unconnected-(U11-DIO2-Pad16)") (class "Default")
      (node (ref "U11") (pin "16") (pinfunction "DIO2_16") (pintype "passive"))
    )
    (net (code "112") (name "unconnected-(U11-DIO3-Pad11)") (class "Default")
      (node (ref "U11") (pin "11") (pinfunction "DIO3_11") (pintype "passive"))
    )
    (net (code "113") (name "unconnected-(U11-DIO4-Pad12)") (class "Default")
      (node (ref "U11") (pin "12") (pinfunction "DIO4_12") (pintype "passive"))
    )
    (net (code "114") (name "unconnected-(U11-DIO5-Pad7)") (class "Default")
      (node (ref "U11") (pin "7") (pinfunction "DIO5_7") (pintype "passive"))
    )
  )
)
